# bikeledwheel.net
KiCad netlist of a schematic drawn in EAGLE
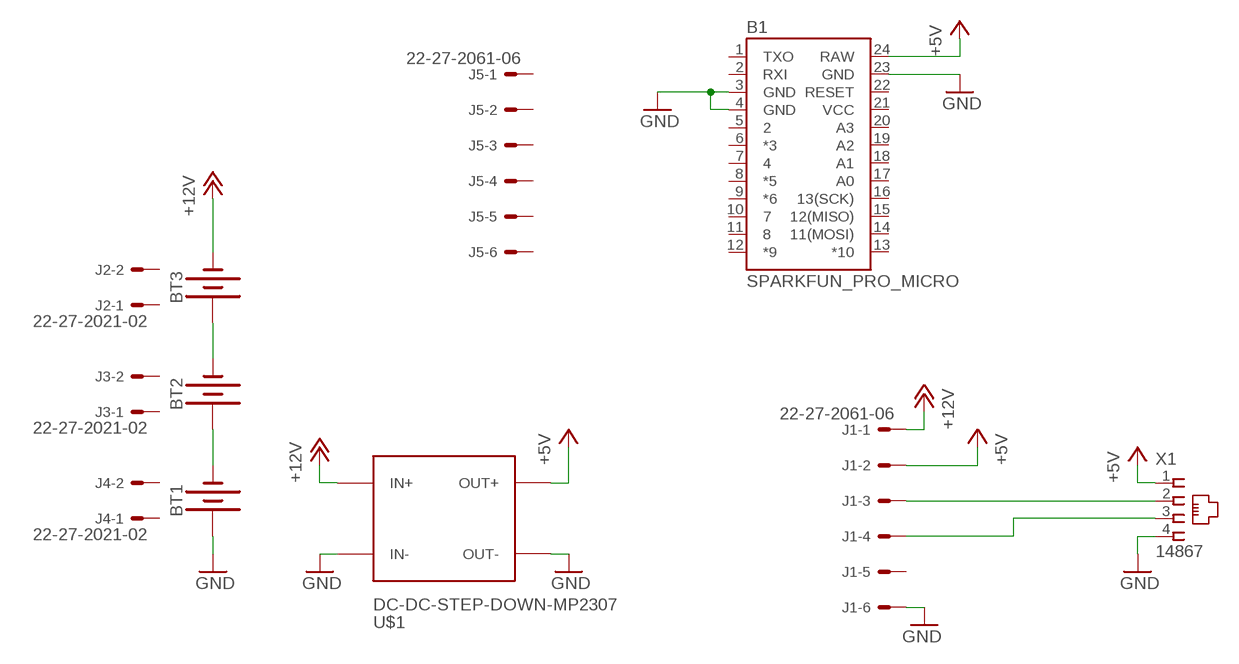
[diagram p0: schematic, sheet 1]

(export (version "E")
  (design (tool "Eeschema 10.0.6"))
  (components
    (comp (ref "B1")
      (value "SPARKFUN_PRO_MICRO")
      (footprint "eagle-import:SPARKFUN_PRO_MICRO")
      (libsource (lib "eagle-import") (part "SPARKFUN_PRO_MICRO"))
    )
    (comp (ref "BT1")
      (value "BATTERY-18650")
      (footprint "eagle-import:BATTERY_18650-HOLDER")
      (libsource (lib "eagle-import") (part "BATTERY-18650"))
    )
    (comp (ref "BT2")
      (value "BATTERY-18650")
      (footprint "eagle-import:BATTERY_18650-HOLDER")
      (libsource (lib "eagle-import") (part "BATTERY-18650"))
    )
    (comp (ref "BT3")
      (value "BATTERY-18650")
      (footprint "eagle-import:BATTERY_18650-HOLDER")
      (libsource (lib "eagle-import") (part "BATTERY-18650"))
    )
    (comp (ref "J1")
      (value "22-27-2061-06")
      (footprint "eagle-import:6410-06")
      (fields (field (name "MF") "MOLEX"))
      (libsource (lib "eagle-import") (part "22-?-0627-2061"))
    )
    (comp (ref "J2")
      (value "22-27-2021-02")
      (footprint "eagle-import:6410-02")
      (fields (field (name "MF") "MOLEX"))
      (libsource (lib "eagle-import") (part "22-?-0227-2021"))
    )
    (comp (ref "J3")
      (value "22-27-2021-02")
      (footprint "eagle-import:6410-02")
      (fields (field (name "MF") "MOLEX"))
      (libsource (lib "eagle-import") (part "22-?-0227-2021"))
    )
    (comp (ref "J4")
      (value "22-27-2021-02")
      (footprint "eagle-import:6410-02")
      (fields (field (name "MF") "MOLEX"))
      (libsource (lib "eagle-import") (part "22-?-0227-2021"))
    )
    (comp (ref "J5")
      (value "22-27-2061-06")
      (footprint "eagle-import:6410-06")
      (fields (field (name "MF") "MOLEX"))
      (libsource (lib "eagle-import") (part "22-?-0627-2061"))
    )
    (comp (ref "U$1")
      (value "DC-DC-STEP-DOWN-MP2307")
      (footprint "eagle-import:DC-DC-STEP-DOWN-MP2307")
      (libsource (lib "eagle-import") (part "DC-DC-STEP-DOWN-MP2307"))
    )
    (comp (ref "X1")
      (value "14867")
      (footprint "eagle-import:14867")
      (libsource (lib "eagle-import") (part "14867"))
    )
  )
  (nets
    (net (code "1") (name "+5V") (class "Default")
      (node (ref "B1") (pin "24") (pinfunction "RAW_24") (pintype "power_in"))
      (node (ref "J1") (pin "2") (pinfunction "S_2") (pintype "passive"))
      (node (ref "U$1") (pin "OUT+") (pinfunction "OUT+_OUT+") (pintype "bidirectional"))
      (node (ref "X1") (pin "1") (pinfunction "1_1") (pintype "passive"))
    )
    (net (code "2") (name "+12V") (class "Default")
      (node (ref "BT3") (pin "GND@1") (pinfunction "-_GND@1") (pintype "power_in"))
      (node (ref "J1") (pin "1") (pinfunction "S_1") (pintype "passive"))
      (node (ref "U$1") (pin "IN+") (pinfunction "IN+_IN+") (pintype "bidirectional"))
    )
    (net (code "3") (name "/VCC") (class "Default")
      (node (ref "B1") (pin "21") (pinfunction "VCC_21") (pintype "power_in"))
    )
    (net (code "4") (name "GND") (class "Default")
      (node (ref "B1") (pin "23") (pinfunction "GND_23") (pintype "power_in"))
      (node (ref "B1") (pin "3") (pinfunction "GND_3") (pintype "power_in"))
      (node (ref "B1") (pin "4") (pinfunction "GND_4") (pintype "power_in"))
      (node (ref "BT1") (pin "PWR@1") (pinfunction "+_PWR@1") (pintype "power_in"))
      (node (ref "J1") (pin "6") (pinfunction "S_6") (pintype "passive"))
      (node (ref "U$1") (pin "IN-") (pinfunction "IN-_IN-") (pintype "bidirectional"))
      (node (ref "U$1") (pin "OUT-") (pinfunction "OUT-_OUT-") (pintype "bidirectional"))
      (node (ref "X1") (pin "4") (pinfunction "4_4") (pintype "passive"))
    )
    (net (code "5") (name "Net-(BT1--)") (class "Default")
      (node (ref "BT1") (pin "GND@1") (pinfunction "-_GND@1") (pintype "power_in"))
      (node (ref "BT2") (pin "PWR@1") (pinfunction "+_PWR@1") (pintype "power_in"))
    )
    (net (code "6") (name "Net-(BT2--)") (class "Default")
      (node (ref "BT2") (pin "GND@1") (pinfunction "-_GND@1") (pintype "power_in"))
      (node (ref "BT3") (pin "PWR@1") (pinfunction "+_PWR@1") (pintype "power_in"))
    )
    (net (code "7") (name "Net-(J1C-S)") (class "Default")
      (node (ref "J1") (pin "3") (pinfunction "S_3") (pintype "passive"))
      (node (ref "X1") (pin "2") (pinfunction "2_2") (pintype "passive"))
    )
    (net (code "8") (name "Net-(J1D-S)") (class "Default")
      (node (ref "J1") (pin "4") (pinfunction "S_4") (pintype "passive"))
      (node (ref "X1") (pin "3") (pinfunction "3_3") (pintype "passive"))
    )
    (net (code "9") (name "unconnected-(B1-*3-Pad6)") (class "Default")
      (node (ref "B1") (pin "6") (pinfunction "*3_6") (pintype "bidirectional"))
    )
    (net (code "10") (name "unconnected-(B1-*5-Pad8)") (class "Default")
      (node (ref "B1") (pin "8") (pinfunction "*5_8") (pintype "bidirectional"))
    )
    (net (code "11") (name "unconnected-(B1-*6-Pad9)") (class "Default")
      (node (ref "B1") (pin "9") (pinfunction "*6_9") (pintype "bidirectional"))
    )
    (net (code "12") (name "unconnected-(B1-*9-Pad12)") (class "Default")
      (node (ref "B1") (pin "12") (pinfunction "*9_12") (pintype "bidirectional"))
    )
    (net (code "13") (name "unconnected-(B1-*10-Pad13)") (class "Default")
      (node (ref "B1") (pin "13") (pinfunction "*10_13") (pintype "bidirectional"))
    )
    (net (code "14") (name "unconnected-(B1-2-Pad5)") (class "Default")
      (node (ref "B1") (pin "5") (pinfunction "2_5") (pintype "bidirectional"))
    )
    (net (code "15") (name "unconnected-(B1-4-Pad7)") (class "Default")
      (node (ref "B1") (pin "7") (pinfunction "4_7") (pintype "bidirectional"))
    )
    (net (code "16") (name "unconnected-(B1-7-Pad10)") (class "Default")
      (node (ref "B1") (pin "10") (pinfunction "7_10") (pintype "bidirectional"))
    )
    (net (code "17") (name "unconnected-(B1-8-Pad11)") (class "Default")
      (node (ref "B1") (pin "11") (pinfunction "8_11") (pintype "bidirectional"))
    )
    (net (code "18") (name "unconnected-(B1-11(MOSI)-Pad14)") (class "Default")
      (node (ref "B1") (pin "14") (pinfunction "11(MOSI)_14") (pintype "bidirectional"))
    )
    (net (code "19") (name "unconnected-(B1-12(MISO)-Pad15)") (class "Default")
      (node (ref "B1") (pin "15") (pinfunction "12(MISO)_15") (pintype "bidirectional"))
    )
    (net (code "20") (name "unconnected-(B1-13(SCK)-Pad16)") (class "Default")
      (node (ref "B1") (pin "16") (pinfunction "13(SCK)_16") (pintype "bidirectional"))
    )
    (net (code "21") (name "unconnected-(B1-A0-Pad17)") (class "Default")
      (node (ref "B1") (pin "17") (pinfunction "A0_17") (pintype "bidirectional"))
    )
    (net (code "22") (name "unconnected-(B1-A1-Pad18)") (class "Default")
      (node (ref "B1") (pin "18") (pinfunction "A1_18") (pintype "bidirectional"))
    )
    (net (code "23") (name "unconnected-(B1-A2-Pad19)") (class "Default")
      (node (ref "B1") (pin "19") (pinfunction "A2_19") (pintype "bidirectional"))
    )
    (net (code "24") (name "unconnected-(B1-A3-Pad20)") (class "Default")
      (node (ref "B1") (pin "20") (pinfunction "A3_20") (pintype "bidirectional"))
    )
    (net (code "25") (name "unconnected-(B1-RESET-Pad22)") (class "Default")
      (node (ref "B1") (pin "22") (pinfunction "RESET_22") (pintype "bidirectional"))
    )
    (net (code "26") (name "unconnected-(B1-RXI-Pad2)") (class "Default")
      (node (ref "B1") (pin "2") (pinfunction "RXI_2") (pintype "bidirectional"))
    )
    (net (code "27") (name "unconnected-(B1-TXO-Pad1)") (class "Default")
      (node (ref "B1") (pin "1") (pinfunction "TXO_1") (pintype "bidirectional"))
    )
    (net (code "28") (name "unconnected-(J1E-S-Pad5)") (class "Default")
      (node (ref "J1") (pin "5") (pinfunction "S_5") (pintype "passive"))
    )
    (net (code "29") (name "unconnected-(J2A-S-Pad1)") (class "Default")
      (node (ref "J2") (pin "1") (pinfunction "S_1") (pintype "passive"))
    )
    (net (code "30") (name "unconnected-(J2B-S-Pad2)") (class "Default")
      (node (ref "J2") (pin "2") (pinfunction "S_2") (pintype "passive"))
    )
    (net (code "31") (name "unconnected-(J3A-S-Pad1)") (class "Default")
      (node (ref "J3") (pin "1") (pinfunction "S_1") (pintype "passive"))
    )
    (net (code "32") (name "unconnected-(J3B-S-Pad2)") (class "Default")
      (node (ref "J3") (pin "2") (pinfunction "S_2") (pintype "passive"))
    )
    (net (code "33") (name "unconnected-(J4A-S-Pad1)") (class "Default")
      (node (ref "J4") (pin "1") (pinfunction "S_1") (pintype "passive"))
    )
    (net (code "34") (name "unconnected-(J4B-S-Pad2)") (class "Default")
      (node (ref "J4") (pin "2") (pinfunction "S_2") (pintype "passive"))
    )
    (net (code "35") (name "unconnected-(J5A-S-Pad1)") (class "Default")
      (node (ref "J5") (pin "1") (pinfunction "S_1") (pintype "passive"))
    )
    (net (code "36") (name "unconnected-(J5B-S-Pad2)") (class "Default")
      (node (ref "J5") (pin "2") (pinfunction "S_2") (pintype "passive"))
    )
    (net (code "37") (name "unconnected-(J5C-S-Pad3)") (class "Default")
      (node (ref "J5") (pin "3") (pinfunction "S_3") (pintype "passive"))
    )
    (net (code "38") (name "unconnected-(J5D-S-Pad4)") (class "Default")
      (node (ref "J5") (pin "4") (pinfunction "S_4") (pintype "passive"))
    )
    (net (code "39") (name "unconnected-(J5E-S-Pad5)") (class "Default")
      (node (ref "J5") (pin "5") (pinfunction "S_5") (pintype "passive"))
    )
    (net (code "40") (name "unconnected-(J5F-S-Pad6)") (class "Default")
      (node (ref "J5") (pin "6") (pinfunction "S_6") (pintype "passive"))
    )
  )
)
